# avrusb500.net
KiCad netlist of a schematic drawn in EAGLE
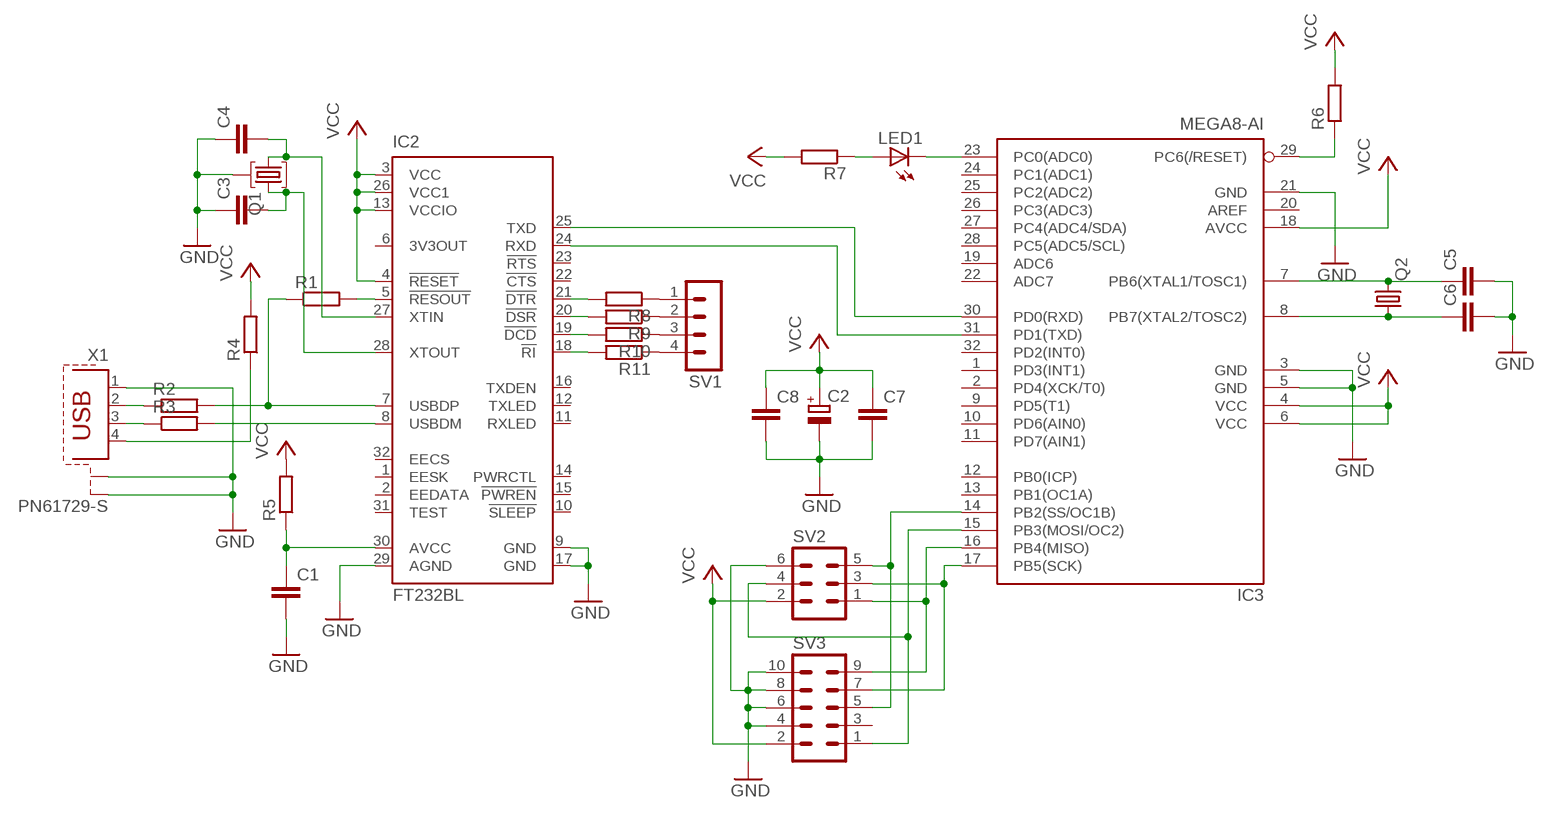
[diagram p0: schematic, sheet 1]

(export (version "E")
  (design (tool "Eeschema 10.0.6"))
  (components
    (comp (ref "C1")
      (value "C-EUC0805")
      (footprint "eagle-import:C0805")
      (libsource (lib "eagle-import") (part "C-EUC0805"))
    )
    (comp (ref "C2")
      (value "CPOL-EUSMCB")
      (footprint "eagle-import:SMC_B")
      (libsource (lib "eagle-import") (part "CPOL-EUSMCB"))
    )
    (comp (ref "C3")
      (value "C-EUC0805")
      (footprint "eagle-import:C0805")
      (libsource (lib "eagle-import") (part "C-EUC0805"))
    )
    (comp (ref "C4")
      (value "C-EUC0805")
      (footprint "eagle-import:C0805")
      (libsource (lib "eagle-import") (part "C-EUC0805"))
    )
    (comp (ref "C5")
      (value "C-EUC0805")
      (footprint "eagle-import:C0805")
      (libsource (lib "eagle-import") (part "C-EUC0805"))
    )
    (comp (ref "C6")
      (value "C-EUC0805")
      (footprint "eagle-import:C0805")
      (libsource (lib "eagle-import") (part "C-EUC0805"))
    )
    (comp (ref "C7")
      (value "C-EUC0805")
      (footprint "eagle-import:C0805")
      (libsource (lib "eagle-import") (part "C-EUC0805"))
    )
    (comp (ref "C8")
      (value "C-EUC0805")
      (footprint "eagle-import:C0805")
      (libsource (lib "eagle-import") (part "C-EUC0805"))
    )
    (comp (ref "IC2")
      (value "FT232BL")
      (footprint "eagle-import:LQFP32-7X7")
      (fields (field (name "MF") "FARNELL") (field (name "MPN") "FT232BL/TR"))
      (libsource (lib "eagle-import") (part "FT232BL"))
    )
    (comp (ref "IC3")
      (value "MEGA8-AI")
      (footprint "eagle-import:TQFP32-08")
      (fields (field (name "MPN") "ATMEGA8-16AU"))
      (libsource (lib "eagle-import") (part "MEGA8-AI"))
    )
    (comp (ref "LED1")
      (value "LED5MM")
      (footprint "eagle-import:LED5MM")
      (libsource (lib "eagle-import") (part "LED5MM"))
    )
    (comp (ref "Q1")
      (value "HC49TL-H")
      (footprint "eagle-import:HC49TL-H")
      (libsource (lib "eagle-import") (part "HC49TL-H"))
    )
    (comp (ref "Q2")
      (value "CRYSTALHC49UP")
      (footprint "eagle-import:HC49UP")
      (libsource (lib "eagle-import") (part "CRYSTALHC49UP"))
    )
    (comp (ref "R1")
      (value "R-EU_R0805")
      (footprint "eagle-import:R0805")
      (libsource (lib "eagle-import") (part "R-EU_R0805"))
    )
    (comp (ref "R2")
      (value "R-EU_R0805")
      (footprint "eagle-import:R0805")
      (libsource (lib "eagle-import") (part "R-EU_R0805"))
    )
    (comp (ref "R3")
      (value "R-EU_R0805")
      (footprint "eagle-import:R0805")
      (libsource (lib "eagle-import") (part "R-EU_R0805"))
    )
    (comp (ref "R4")
      (value "R-EU_R0805")
      (footprint "eagle-import:R0805")
      (libsource (lib "eagle-import") (part "R-EU_R0805"))
    )
    (comp (ref "R5")
      (value "R-EU_R0805")
      (footprint "eagle-import:R0805")
      (libsource (lib "eagle-import") (part "R-EU_R0805"))
    )
    (comp (ref "R6")
      (value "R-EU_R0805")
      (footprint "eagle-import:R0805")
      (libsource (lib "eagle-import") (part "R-EU_R0805"))
    )
    (comp (ref "R7")
      (value "R-EU_R0805")
      (footprint "eagle-import:R0805")
      (libsource (lib "eagle-import") (part "R-EU_R0805"))
    )
    (comp (ref "R8")
      (value "R-EU_R0805")
      (footprint "eagle-import:R0805")
      (libsource (lib "eagle-import") (part "R-EU_R0805"))
    )
    (comp (ref "R9")
      (value "R-EU_R0805")
      (footprint "eagle-import:R0805")
      (libsource (lib "eagle-import") (part "R-EU_R0805"))
    )
    (comp (ref "R10")
      (value "R-EU_R0805")
      (footprint "eagle-import:R0805")
      (libsource (lib "eagle-import") (part "R-EU_R0805"))
    )
    (comp (ref "R11")
      (value "R-EU_R0805")
      (footprint "eagle-import:R0805")
      (libsource (lib "eagle-import") (part "R-EU_R0805"))
    )
    (comp (ref "SV1")
      (value "MA04-1")
      (footprint "eagle-import:MA04-1")
      (libsource (lib "eagle-import") (part "MA04-1"))
    )
    (comp (ref "SV2")
      (value "ML6L")
      (footprint "eagle-import:ML6L")
      (libsource (lib "eagle-import") (part "ML6L"))
    )
    (comp (ref "SV3")
      (value "ML10L")
      (footprint "eagle-import:ML10L")
      (libsource (lib "eagle-import") (part "ML10L"))
    )
    (comp (ref "X1")
      (value "PN61729-S")
      (footprint "eagle-import:PN61729-S")
      (libsource (lib "eagle-import") (part "PN61729-S"))
    )
  )
  (nets
    (net (code "1") (name "GND") (class "Default")
      (node (ref "C1") (pin "2") (pinfunction "2_2") (pintype "passive"))
      (node (ref "C2") (pin "-") (pinfunction "-_-") (pintype "passive"))
      (node (ref "C3") (pin "1") (pinfunction "1_1") (pintype "passive"))
      (node (ref "C4") (pin "1") (pinfunction "1_1") (pintype "passive"))
      (node (ref "C5") (pin "2") (pinfunction "2_2") (pintype "passive"))
      (node (ref "C6") (pin "2") (pinfunction "2_2") (pintype "passive"))
      (node (ref "C7") (pin "2") (pinfunction "2_2") (pintype "passive"))
      (node (ref "C8") (pin "2") (pinfunction "2_2") (pintype "passive"))
      (node (ref "IC2") (pin "17") (pinfunction "GND_17") (pintype "power_in"))
      (node (ref "IC2") (pin "29") (pinfunction "AGND_29") (pintype "power_in"))
      (node (ref "IC2") (pin "9") (pinfunction "GND_9") (pintype "power_in"))
      (node (ref "IC3") (pin "21") (pinfunction "GND_21") (pintype "power_in"))
      (node (ref "IC3") (pin "3") (pinfunction "GND_3") (pintype "power_in"))
      (node (ref "IC3") (pin "5") (pinfunction "GND_5") (pintype "power_in"))
      (node (ref "Q1") (pin "3") (pinfunction "3_3") (pintype "passive"))
      (node (ref "SV2") (pin "6") (pinfunction "6_6") (pintype "passive"))
      (node (ref "SV3") (pin "10") (pinfunction "10_10") (pintype "passive"))
      (node (ref "SV3") (pin "4") (pinfunction "4_4") (pintype "passive"))
      (node (ref "SV3") (pin "6") (pinfunction "6_6") (pintype "passive"))
      (node (ref "SV3") (pin "8") (pinfunction "8_8") (pintype "passive"))
      (node (ref "X1") (pin "1") (pinfunction "1_1") (pintype "passive"))
      (node (ref "X1") (pin "S1") (pinfunction "S1_S1") (pintype "passive"))
      (node (ref "X1") (pin "S2") (pinfunction "S2_S2") (pintype "passive"))
    )
    (net (code "2") (name "Net-(IC2-AVCC)") (class "Default")
      (node (ref "C1") (pin "1") (pinfunction "1_1") (pintype "passive"))
      (node (ref "IC2") (pin "30") (pinfunction "AVCC_30") (pintype "power_in"))
      (node (ref "R5") (pin "1") (pinfunction "1_1") (pintype "passive"))
    )
    (net (code "3") (name "Net-(IC2-RXD)") (class "Default")
      (node (ref "IC2") (pin "24") (pinfunction "RXD_24") (pintype "input"))
      (node (ref "IC3") (pin "31") (pinfunction "PD1(TXD)_31") (pintype "bidirectional"))
    )
    (net (code "4") (name "Net-(IC2-TXD)") (class "Default")
      (node (ref "IC2") (pin "25") (pinfunction "TXD_25") (pintype "output"))
      (node (ref "IC3") (pin "30") (pinfunction "PD0(RXD)_30") (pintype "bidirectional"))
    )
    (net (code "5") (name "Net-(IC2-USBDM)") (class "Default")
      (node (ref "IC2") (pin "8") (pinfunction "USBDM_8") (pintype "bidirectional"))
      (node (ref "R3") (pin "2") (pinfunction "2_2") (pintype "passive"))
    )
    (net (code "6") (name "Net-(IC2-USBDP)") (class "Default")
      (node (ref "IC2") (pin "7") (pinfunction "USBDP_7") (pintype "bidirectional"))
      (node (ref "R1") (pin "1") (pinfunction "1_1") (pintype "passive"))
      (node (ref "R2") (pin "2") (pinfunction "2_2") (pintype "passive"))
    )
    (net (code "7") (name "Net-(IC2-XTIN)") (class "Default")
      (node (ref "C4") (pin "2") (pinfunction "2_2") (pintype "passive"))
      (node (ref "IC2") (pin "27") (pinfunction "XTIN_27") (pintype "input"))
      (node (ref "Q1") (pin "1") (pinfunction "1_1") (pintype "passive"))
    )
    (net (code "8") (name "Net-(IC2-XTOUT)") (class "Default")
      (node (ref "C3") (pin "2") (pinfunction "2_2") (pintype "passive"))
      (node (ref "IC2") (pin "28") (pinfunction "XTOUT_28") (pintype "output"))
      (node (ref "Q1") (pin "2") (pinfunction "2_2") (pintype "passive"))
    )
    (net (code "9") (name "Net-(IC2-~{DCD})") (class "Default")
      (node (ref "IC2") (pin "19") (pinfunction "~{DCD}_19") (pintype "input"))
      (node (ref "R10") (pin "2") (pinfunction "2_2") (pintype "passive"))
    )
    (net (code "10") (name "Net-(IC2-~{DSR})") (class "Default")
      (node (ref "IC2") (pin "20") (pinfunction "~{DSR}_20") (pintype "input"))
      (node (ref "R9") (pin "2") (pinfunction "2_2") (pintype "passive"))
    )
    (net (code "11") (name "Net-(IC2-~{DTR})") (class "Default")
      (node (ref "IC2") (pin "21") (pinfunction "~{DTR}_21") (pintype "output"))
      (node (ref "R8") (pin "2") (pinfunction "2_2") (pintype "passive"))
    )
    (net (code "12") (name "Net-(IC2-~{RESOUT})") (class "Default")
      (node (ref "IC2") (pin "5") (pinfunction "~{RESOUT}_5") (pintype "input"))
      (node (ref "R1") (pin "2") (pinfunction "2_2") (pintype "passive"))
    )
    (net (code "13") (name "Net-(IC2-~{RI})") (class "Default")
      (node (ref "IC2") (pin "18") (pinfunction "~{RI}_18") (pintype "input"))
      (node (ref "R11") (pin "2") (pinfunction "2_2") (pintype "passive"))
    )
    (net (code "14") (name "Net-(IC3-PB2(SS{slash}OC1B))") (class "Default")
      (node (ref "IC3") (pin "14") (pinfunction "PB2(SS/OC1B)_14") (pintype "bidirectional"))
      (node (ref "SV2") (pin "5") (pinfunction "5_5") (pintype "passive"))
      (node (ref "SV3") (pin "5") (pinfunction "5_5") (pintype "passive"))
    )
    (net (code "15") (name "Net-(IC3-PB3(MOSI{slash}OC2))") (class "Default")
      (node (ref "IC3") (pin "15") (pinfunction "PB3(MOSI/OC2)_15") (pintype "bidirectional"))
      (node (ref "SV2") (pin "4") (pinfunction "4_4") (pintype "passive"))
      (node (ref "SV3") (pin "1") (pinfunction "1_1") (pintype "passive"))
    )
    (net (code "16") (name "Net-(IC3-PB4(MISO))") (class "Default")
      (node (ref "IC3") (pin "16") (pinfunction "PB4(MISO)_16") (pintype "bidirectional"))
      (node (ref "SV2") (pin "1") (pinfunction "1_1") (pintype "passive"))
      (node (ref "SV3") (pin "9") (pinfunction "9_9") (pintype "passive"))
    )
    (net (code "17") (name "Net-(IC3-PB5(SCK))") (class "Default")
      (node (ref "IC3") (pin "17") (pinfunction "PB5(SCK)_17") (pintype "bidirectional"))
      (node (ref "SV2") (pin "3") (pinfunction "3_3") (pintype "passive"))
      (node (ref "SV3") (pin "7") (pinfunction "7_7") (pintype "passive"))
    )
    (net (code "18") (name "Net-(IC3-PB6(XTAL1{slash}TOSC1))") (class "Default")
      (node (ref "C5") (pin "1") (pinfunction "1_1") (pintype "passive"))
      (node (ref "IC3") (pin "7") (pinfunction "PB6(XTAL1/TOSC1)_7") (pintype "bidirectional"))
      (node (ref "Q2") (pin "2") (pinfunction "2_2") (pintype "passive"))
    )
    (net (code "19") (name "Net-(IC3-PB7(XTAL2{slash}TOSC2))") (class "Default")
      (node (ref "C6") (pin "1") (pinfunction "1_1") (pintype "passive"))
      (node (ref "IC3") (pin "8") (pinfunction "PB7(XTAL2/TOSC2)_8") (pintype "bidirectional"))
      (node (ref "Q2") (pin "1") (pinfunction "1_1") (pintype "passive"))
    )
    (net (code "20") (name "Net-(IC3-PC0(ADC0))") (class "Default")
      (node (ref "IC3") (pin "23") (pinfunction "PC0(ADC0)_23") (pintype "bidirectional"))
      (node (ref "LED1") (pin "K") (pinfunction "C_K") (pintype "passive"))
    )
    (net (code "21") (name "Net-(IC3-PC6({slash}RESET))") (class "Default")
      (node (ref "IC3") (pin "29") (pinfunction "PC6(/RESET)_29") (pintype "bidirectional"))
      (node (ref "R6") (pin "1") (pinfunction "1_1") (pintype "passive"))
    )
    (net (code "22") (name "Net-(LED1-PadA)") (class "Default")
      (node (ref "LED1") (pin "A") (pinfunction "A_A") (pintype "passive"))
      (node (ref "R7") (pin "1") (pinfunction "1_1") (pintype "passive"))
    )
    (net (code "23") (name "Net-(R2-Pad1)") (class "Default")
      (node (ref "R2") (pin "1") (pinfunction "1_1") (pintype "passive"))
      (node (ref "X1") (pin "2") (pinfunction "2_2") (pintype "passive"))
    )
    (net (code "24") (name "Net-(R3-Pad1)") (class "Default")
      (node (ref "R3") (pin "1") (pinfunction "1_1") (pintype "passive"))
      (node (ref "X1") (pin "3") (pinfunction "3_3") (pintype "passive"))
    )
    (net (code "25") (name "Net-(R4-Pad1)") (class "Default")
      (node (ref "R4") (pin "1") (pinfunction "1_1") (pintype "passive"))
      (node (ref "X1") (pin "4") (pinfunction "4_4") (pintype "passive"))
    )
    (net (code "26") (name "Net-(R8-Pad1)") (class "Default")
      (node (ref "R8") (pin "1") (pinfunction "1_1") (pintype "passive"))
      (node (ref "SV1") (pin "1") (pinfunction "1_1") (pintype "passive"))
    )
    (net (code "27") (name "Net-(R9-Pad1)") (class "Default")
      (node (ref "R9") (pin "1") (pinfunction "1_1") (pintype "passive"))
      (node (ref "SV1") (pin "2") (pinfunction "2_2") (pintype "passive"))
    )
    (net (code "28") (name "Net-(R10-Pad1)") (class "Default")
      (node (ref "R10") (pin "1") (pinfunction "1_1") (pintype "passive"))
      (node (ref "SV1") (pin "3") (pinfunction "3_3") (pintype "passive"))
    )
    (net (code "29") (name "Net-(R11-Pad1)") (class "Default")
      (node (ref "R11") (pin "1") (pinfunction "1_1") (pintype "passive"))
      (node (ref "SV1") (pin "4") (pinfunction "4_4") (pintype "passive"))
    )
    (net (code "30") (name "VCC") (class "Default")
      (node (ref "C2") (pin "+") (pinfunction "+_+") (pintype "passive"))
      (node (ref "C7") (pin "1") (pinfunction "1_1") (pintype "passive"))
      (node (ref "C8") (pin "1") (pinfunction "1_1") (pintype "passive"))
      (node (ref "IC2") (pin "13") (pinfunction "VCCIO_13") (pintype "power_in"))
      (node (ref "IC2") (pin "26") (pinfunction "VCC1_26") (pintype "power_in"))
      (node (ref "IC2") (pin "3") (pinfunction "VCC_3") (pintype "power_in"))
      (node (ref "IC2") (pin "4") (pinfunction "~{RESET}_4") (pintype "input"))
      (node (ref "IC3") (pin "18") (pinfunction "AVCC_18") (pintype "power_in"))
      (node (ref "IC3") (pin "4") (pinfunction "VCC_4") (pintype "power_in"))
      (node (ref "IC3") (pin "6") (pinfunction "VCC_6") (pintype "power_in"))
      (node (ref "R4") (pin "2") (pinfunction "2_2") (pintype "passive"))
      (node (ref "R5") (pin "2") (pinfunction "2_2") (pintype "passive"))
      (node (ref "R6") (pin "2") (pinfunction "2_2") (pintype "passive"))
      (node (ref "R7") (pin "2") (pinfunction "2_2") (pintype "passive"))
      (node (ref "SV2") (pin "2") (pinfunction "2_2") (pintype "passive"))
      (node (ref "SV3") (pin "2") (pinfunction "2_2") (pintype "passive"))
    )
    (net (code "31") (name "unconnected-(IC2-3V3OUT-Pad6)") (class "Default")
      (node (ref "IC2") (pin "6") (pinfunction "3V3OUT_6") (pintype "output"))
    )
    (net (code "32") (name "unconnected-(IC2-EECS-Pad32)") (class "Default")
      (node (ref "IC2") (pin "32") (pinfunction "EECS_32") (pintype "input"))
    )
    (net (code "33") (name "unconnected-(IC2-EEDATA-Pad2)") (class "Default")
      (node (ref "IC2") (pin "2") (pinfunction "EEDATA_2") (pintype "input"))
    )
    (net (code "34") (name "unconnected-(IC2-EESK-Pad1)") (class "Default")
      (node (ref "IC2") (pin "1") (pinfunction "EESK_1") (pintype "input"))
    )
    (net (code "35") (name "unconnected-(IC2-PWRCTL-Pad14)") (class "Default")
      (node (ref "IC2") (pin "14") (pinfunction "PWRCTL_14") (pintype "bidirectional"))
    )
    (net (code "36") (name "unconnected-(IC2-RXLED-Pad11)") (class "Default")
      (node (ref "IC2") (pin "11") (pinfunction "RXLED_11") (pintype "bidirectional"))
    )
    (net (code "37") (name "unconnected-(IC2-TEST-Pad31)") (class "Default")
      (node (ref "IC2") (pin "31") (pinfunction "TEST_31") (pintype "input"))
    )
    (net (code "38") (name "unconnected-(IC2-TXDEN-Pad16)") (class "Default")
      (node (ref "IC2") (pin "16") (pinfunction "TXDEN_16") (pintype "bidirectional"))
    )
    (net (code "39") (name "unconnected-(IC2-TXLED-Pad12)") (class "Default")
      (node (ref "IC2") (pin "12") (pinfunction "TXLED_12") (pintype "bidirectional"))
    )
    (net (code "40") (name "unconnected-(IC2-~{CTS}-Pad22)") (class "Default")
      (node (ref "IC2") (pin "22") (pinfunction "~{CTS}_22") (pintype "input"))
    )
    (net (code "41") (name "unconnected-(IC2-~{PWREN}-Pad15)") (class "Default")
      (node (ref "IC2") (pin "15") (pinfunction "~{PWREN}_15") (pintype "bidirectional"))
    )
    (net (code "42") (name "unconnected-(IC2-~{RTS}-Pad23)") (class "Default")
      (node (ref "IC2") (pin "23") (pinfunction "~{RTS}_23") (pintype "output"))
    )
    (net (code "43") (name "unconnected-(IC2-~{SLEEP}-Pad10)") (class "Default")
      (node (ref "IC2") (pin "10") (pinfunction "~{SLEEP}_10") (pintype "input"))
    )
    (net (code "44") (name "unconnected-(IC3-ADC6-Pad19)") (class "Default")
      (node (ref "IC3") (pin "19") (pinfunction "ADC6_19") (pintype "bidirectional"))
    )
    (net (code "45") (name "unconnected-(IC3-ADC7-Pad22)") (class "Default")
      (node (ref "IC3") (pin "22") (pinfunction "ADC7_22") (pintype "bidirectional"))
    )
    (net (code "46") (name "unconnected-(IC3-AREF-Pad20)") (class "Default")
      (node (ref "IC3") (pin "20") (pinfunction "AREF_20") (pintype "passive"))
    )
    (net (code "47") (name "unconnected-(IC3-PB0(ICP)-Pad12)") (class "Default")
      (node (ref "IC3") (pin "12") (pinfunction "PB0(ICP)_12") (pintype "bidirectional"))
    )
    (net (code "48") (name "unconnected-(IC3-PB1(OC1A)-Pad13)") (class "Default")
      (node (ref "IC3") (pin "13") (pinfunction "PB1(OC1A)_13") (pintype "bidirectional"))
    )
    (net (code "49") (name "unconnected-(IC3-PC1(ADC1)-Pad24)") (class "Default")
      (node (ref "IC3") (pin "24") (pinfunction "PC1(ADC1)_24") (pintype "bidirectional"))
    )
    (net (code "50") (name "unconnected-(IC3-PC2(ADC2)-Pad25)") (class "Default")
      (node (ref "IC3") (pin "25") (pinfunction "PC2(ADC2)_25") (pintype "bidirectional"))
    )
    (net (code "51") (name "unconnected-(IC3-PC3(ADC3)-Pad26)") (class "Default")
      (node (ref "IC3") (pin "26") (pinfunction "PC3(ADC3)_26") (pintype "bidirectional"))
    )
    (net (code "52") (name "unconnected-(IC3-PC4(ADC4{slash}SDA)-Pad27)") (class "Default")
      (node (ref "IC3") (pin "27") (pinfunction "PC4(ADC4/SDA)_27") (pintype "bidirectional"))
    )
    (net (code "53") (name "unconnected-(IC3-PC5(ADC5{slash}SCL)-Pad28)") (class "Default")
      (node (ref "IC3") (pin "28") (pinfunction "PC5(ADC5/SCL)_28") (pintype "bidirectional"))
    )
    (net (code "54") (name "unconnected-(IC3-PD2(INT0)-Pad32)") (class "Default")
      (node (ref "IC3") (pin "32") (pinfunction "PD2(INT0)_32") (pintype "bidirectional"))
    )
    (net (code "55") (name "unconnected-(IC3-PD3(INT1)-Pad1)") (class "Default")
      (node (ref "IC3") (pin "1") (pinfunction "PD3(INT1)_1") (pintype "bidirectional"))
    )
    (net (code "56") (name "unconnected-(IC3-PD4(XCK{slash}T0)-Pad2)") (class "Default")
      (node (ref "IC3") (pin "2") (pinfunction "PD4(XCK/T0)_2") (pintype "bidirectional"))
    )
    (net (code "57") (name "unconnected-(IC3-PD5(T1)-Pad9)") (class "Default")
      (node (ref "IC3") (pin "9") (pinfunction "PD5(T1)_9") (pintype "bidirectional"))
    )
    (net (code "58") (name "unconnected-(IC3-PD6(AIN0)-Pad10)") (class "Default")
      (node (ref "IC3") (pin "10") (pinfunction "PD6(AIN0)_10") (pintype "bidirectional"))
    )
    (net (code "59") (name "unconnected-(IC3-PD7(AIN1)-Pad11)") (class "Default")
      (node (ref "IC3") (pin "11") (pinfunction "PD7(AIN1)_11") (pintype "bidirectional"))
    )
    (net (code "60") (name "unconnected-(SV3-Pad3)") (class "Default")
      (node (ref "SV3") (pin "3") (pinfunction "3_3") (pintype "passive"))
    )
  )
)
